# WDUExtensionBoard.net
KiCad netlist of a schematic drawn in Altium Designer
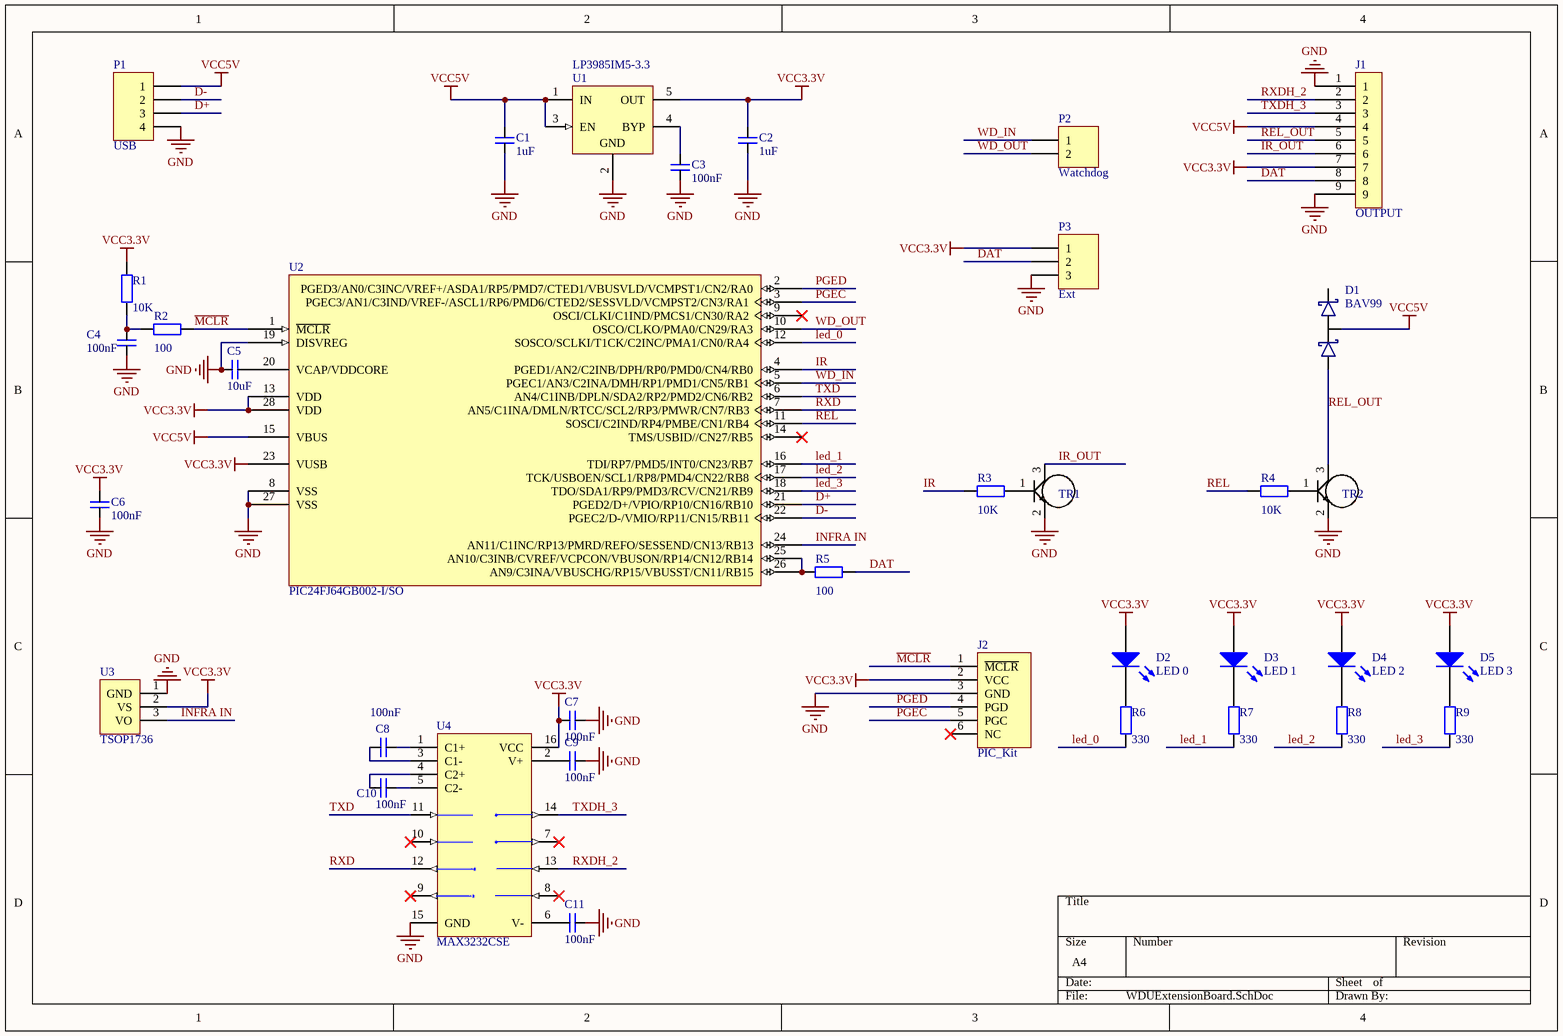
[diagram p0: WDUExtensionBoard.SchDoc]

(export (version "E")
  (design (tool "Eeschema 10.0.6"))
  (components
    (comp (ref "C1")
      (value "1uF")
      (footprint "0805 CAP")
      (description "Capacitor")
      (libsource (lib "EtherIOv2") (part "CAP"))
    )
    (comp (ref "C2")
      (value "1uF")
      (footprint "0805 CAP")
      (description "Capacitor")
      (libsource (lib "EtherIOv2") (part "CAP"))
    )
    (comp (ref "C3")
      (value "100nF")
      (footprint "0805 CAP")
      (description "Capacitor")
      (libsource (lib "EtherIOv2") (part "CAP"))
    )
    (comp (ref "C4")
      (value "100nF")
      (footprint "0805 CAP")
      (description "Capacitor")
      (libsource (lib "EtherIOv2") (part "CAP"))
    )
    (comp (ref "C5")
      (value "10uF")
      (footprint "0805 CAP")
      (description "Capacitor")
      (libsource (lib "EtherIOv2") (part "CAP"))
    )
    (comp (ref "C6")
      (value "100nF")
      (footprint "0805 CAP")
      (description "Capacitor")
      (libsource (lib "EtherIOv2") (part "CAP"))
    )
    (comp (ref "C7")
      (value "100nF")
      (footprint "0805 CAP")
      (description "Capacitor")
      (libsource (lib "EtherIOv2") (part "CAP"))
    )
    (comp (ref "C8")
      (value "100nF")
      (footprint "0805 CAP")
      (description "Capacitor")
      (libsource (lib "EtherIOv2") (part "CAP"))
    )
    (comp (ref "C9")
      (value "100nF")
      (footprint "0805 CAP")
      (description "Capacitor")
      (libsource (lib "EtherIOv2") (part "CAP"))
    )
    (comp (ref "C10")
      (value "100nF")
      (footprint "0805 CAP")
      (description "Capacitor")
      (libsource (lib "EtherIOv2") (part "CAP"))
    )
    (comp (ref "C11")
      (value "100nF")
      (footprint "0805 CAP")
      (description "Capacitor")
      (libsource (lib "EtherIOv2") (part "CAP"))
    )
    (comp (ref "D1")
      (value "BAV99")
      (footprint "SOT23")
      (description "Dual Schottky series - 0.2A, 75V")
      (libsource (lib "EtherIOv2") (part "BAV99"))
    )
    (comp (ref "D2")
      (value "LED 0")
      (footprint "1206 LED Reversed")
      (description "Typical RED, GREEN, YELLOW, AMBER GaAs LED")
      (fields (field (name "PUBLISHER") "Altium Limited"))
      (libsource (lib "Miscellaneous Devices") (part "LED2"))
    )
    (comp (ref "D3")
      (value "LED 1")
      (footprint "1206 LED Reversed")
      (description "Typical RED, GREEN, YELLOW, AMBER GaAs LED")
      (fields (field (name "PUBLISHER") "Altium Limited"))
      (libsource (lib "Miscellaneous Devices") (part "LED2"))
    )
    (comp (ref "D4")
      (value "LED 2")
      (footprint "1206 LED Reversed")
      (description "Typical RED, GREEN, YELLOW, AMBER GaAs LED")
      (fields (field (name "PUBLISHER") "Altium Limited"))
      (libsource (lib "Miscellaneous Devices") (part "LED2"))
    )
    (comp (ref "D5")
      (value "LED 3")
      (footprint "1206 LED Reversed")
      (description "Typical RED, GREEN, YELLOW, AMBER GaAs LED")
      (fields (field (name "PUBLISHER") "Altium Limited"))
      (libsource (lib "Miscellaneous Devices") (part "LED2"))
    )
    (comp (ref "J1")
      (value "OUTPUT")
      (footprint "Euroblock 3.5pitch 9P")
      (libsource (lib "EtherIOv2") (part "Euroblock 9P connector"))
    )
    (comp (ref "J2")
      (value "PIC_Kit")
      (footprint "HDR1X6")
      (description "PIC Kit connector")
      (libsource (lib "EtherIOv2") (part "PIC_Kit"))
    )
    (comp (ref "P1")
      (value "USB")
      (footprint "HDR1X4")
      (description "Header, 4-Pin")
      (fields (field (name "PUBLISHER") "Altium Limited"))
      (libsource (lib "Miscellaneous Connectors") (part "Header 4"))
    )
    (comp (ref "P2")
      (value "Watchdog")
      (footprint "HDR1X2")
      (description "Header, 2-Pin")
      (fields (field (name "PUBLISHER") "Altium Limited"))
      (libsource (lib "Miscellaneous Connectors") (part "Header 2"))
    )
    (comp (ref "P3")
      (value "Ext")
      (footprint "HDR1X3")
      (description "Header, 3-Pin")
      (fields (field (name "PUBLISHER") "Altium Limited"))
      (libsource (lib "Miscellaneous Connectors") (part "Header 3"))
    )
    (comp (ref "R1")
      (value "10K")
      (footprint "0805 RES")
      (description "Resistor")
      (fields (field (name "PUBLISHER") "Altium Limited"))
      (libsource (lib "") (part "RES_2"))
    )
    (comp (ref "R2")
      (value "100")
      (footprint "0805 RES")
      (description "Resistor")
      (fields (field (name "PUBLISHER") "Altium Limited"))
      (libsource (lib "EtherIOv2") (part "RES"))
    )
    (comp (ref "R3")
      (value "10K")
      (footprint "0805 RES")
      (description "Resistor")
      (fields (field (name "PUBLISHER") "Altium Limited"))
      (libsource (lib "EtherIOv2") (part "RES"))
    )
    (comp (ref "R4")
      (value "10K")
      (footprint "0805 RES")
      (description "Resistor")
      (fields (field (name "PUBLISHER") "Altium Limited"))
      (libsource (lib "EtherIOv2") (part "RES"))
    )
    (comp (ref "R5")
      (value "100")
      (footprint "0805 RES")
      (description "Resistor")
      (fields (field (name "PUBLISHER") "Altium Limited"))
      (libsource (lib "EtherIOv2") (part "RES"))
    )
    (comp (ref "R6")
      (value "330")
      (footprint "0805 RES")
      (description "Resistor")
      (fields (field (name "PUBLISHER") "Altium Limited"))
      (libsource (lib "") (part "RES_1"))
    )
    (comp (ref "R7")
      (value "330")
      (footprint "0805 RES")
      (description "Resistor")
      (fields (field (name "PUBLISHER") "Altium Limited"))
      (libsource (lib "") (part "RES_1"))
    )
    (comp (ref "R8")
      (value "330")
      (footprint "0805 RES")
      (description "Resistor")
      (fields (field (name "PUBLISHER") "Altium Limited"))
      (libsource (lib "") (part "RES_1"))
    )
    (comp (ref "R9")
      (value "330")
      (footprint "0805 RES")
      (description "Resistor")
      (fields (field (name "PUBLISHER") "Altium Limited"))
      (libsource (lib "") (part "RES_1"))
    )
    (comp (ref "TR1")
      (value "BC846")
      (footprint "SOT23")
      (description "NPN Transistor, 80 V, SOT23")
      (libsource (lib "Waterstars") (part "BC846"))
    )
    (comp (ref "TR2")
      (value "BC846")
      (footprint "SOT23")
      (description "NPN Transistor, 80 V, SOT23")
      (libsource (lib "Waterstars") (part "BC846"))
    )
    (comp (ref "U1")
      (value "LP3985IM5-3.3")
      (footprint "MF05A_N")
      (description "Micropower, 150mA Low-Noise Ultra Low-Dropout CMOS Voltage Regulator")
      (fields
        (field (name "MANUFACTURER") "National Semiconductor")
        (field (name "DIGIKEYPARTNUMBER") "LP3985IM5-3.3CT-ND")
        (field (name "PUBLISHER") "Altium Limited")
      )
      (libsource (lib "NSC LDO") (part "LP3985IM5-3.3"))
    )
    (comp (ref "U2")
      (value "PIC24FJ64GB002-I/SO")
      (footprint "SSOP-28")
      (fields (field (name "PUBLISHER") "Altium Limited"))
      (libsource (lib "Waterstars") (part "PIC24FJ64GB002-I/SO"))
    )
    (comp (ref "U3")
      (value "TSOP1736")
      (footprint "TSOP17xx")
      (description "IR Receiver, 3-Pin")
      (fields (field (name "PUBLISHER") "Altium Limited"))
      (libsource (lib "EtherIOv2") (part "TSOP17xx"))
    )
    (comp (ref "U4")
      (value "MAX3232CSE")
      (footprint "NSO16_M")
      (description "3.0V TO 5.5V, Low-Power, up to 1Mbps, True RS-232 Transceiver Using Four 0.1µF External Capacitor")
      (fields (field (name "PUBLISHER") "Altium Limited"))
      (libsource (lib "Maxim Communication Transceiver") (part "MAX3232CSE"))
    )
  )
  (nets
    (net (code "1") (name "/D+") (class "Default")
      (node (ref "P1") (pin "3") (pinfunction "3_3") (pintype "passive"))
      (node (ref "U2") (pin "21") (pinfunction "PGED2/D+/VPIO/RP10/CN16/RB10_21") (pintype "bidirectional"))
    )
    (net (code "2") (name "/D-") (class "Default")
      (node (ref "P1") (pin "2") (pinfunction "2_2") (pintype "passive"))
      (node (ref "U2") (pin "22") (pinfunction "PGEC2/D-/VMIO/RP11/CN15/RB11_22") (pintype "bidirectional"))
    )
    (net (code "3") (name "/DAT") (class "Default")
      (node (ref "J1") (pin "8") (pinfunction "8_8") (pintype "passive"))
      (node (ref "P3") (pin "2") (pinfunction "2_2") (pintype "passive"))
      (node (ref "R5") (pin "1") (pinfunction "1_1") (pintype "passive"))
    )
    (net (code "4") (name "/INFRA IN") (class "Default")
      (node (ref "U2") (pin "24") (pinfunction "AN11/C1INC/RP13/PMRD/REFO/SESSEND/CN13/RB13_24") (pintype "bidirectional"))
      (node (ref "U3") (pin "3") (pinfunction "VO_3") (pintype "passive"))
    )
    (net (code "5") (name "/IR") (class "Default")
      (node (ref "R3") (pin "2") (pinfunction "2_2") (pintype "passive"))
      (node (ref "U2") (pin "4") (pinfunction "PGED1/AN2/C2INB/DPH/RP0/PMD0/CN4/RB0_4") (pintype "bidirectional"))
    )
    (net (code "6") (name "/IR_OUT") (class "Default")
      (node (ref "J1") (pin "6") (pinfunction "6_6") (pintype "passive"))
      (node (ref "TR1") (pin "3") (pinfunction "2_3") (pintype "passive"))
    )
    (net (code "7") (name "/PGEC") (class "Default")
      (node (ref "J2") (pin "5") (pinfunction "PGC_5") (pintype "passive"))
      (node (ref "U2") (pin "3") (pinfunction "PGEC3/AN1/C3IND/VREF-/ASCL1/RP6/PMD6/CTED2/SESSVLD/VCMPST2/CN3/RA1_3") (pintype "bidirectional"))
    )
    (net (code "8") (name "/PGED") (class "Default")
      (node (ref "J2") (pin "4") (pinfunction "PGD_4") (pintype "passive"))
      (node (ref "U2") (pin "2") (pinfunction "PGED3/AN0/C3INC/VREF+/ASDA1/RP5/PMD7/CTED1/VBUSVLD/VCMPST1/CN2/RA0_2") (pintype "bidirectional"))
    )
    (net (code "9") (name "/REL") (class "Default")
      (node (ref "R4") (pin "2") (pinfunction "2_2") (pintype "passive"))
      (node (ref "U2") (pin "11") (pinfunction "SOSCI/C2IND/RP4/PMBE/CN1/RB4_11") (pintype "bidirectional"))
    )
    (net (code "10") (name "/REL_OUT") (class "Default")
      (node (ref "D1") (pin "1") (pintype "passive"))
      (node (ref "J1") (pin "5") (pinfunction "5_5") (pintype "passive"))
      (node (ref "TR2") (pin "3") (pinfunction "2_3") (pintype "passive"))
    )
    (net (code "11") (name "/RXD") (class "Default")
      (node (ref "U2") (pin "7") (pinfunction "AN5/C1INA/DMLN/RTCC/SCL2/RP3/PMWR/CN7/RB3_7") (pintype "bidirectional"))
      (node (ref "U4") (pin "12") (pinfunction "R1OUT_12") (pintype "output"))
    )
    (net (code "12") (name "/RXDH_2") (class "Default")
      (node (ref "J1") (pin "2") (pinfunction "2_2") (pintype "passive"))
      (node (ref "U4") (pin "13") (pinfunction "R1IN_13") (pintype "input"))
    )
    (net (code "13") (name "/TXD") (class "Default")
      (node (ref "U2") (pin "6") (pinfunction "AN4/C1INB/DPLN/SDA2/RP2/PMD2/CN6/RB2_6") (pintype "bidirectional"))
      (node (ref "U4") (pin "11") (pinfunction "T1IN_11") (pintype "input"))
    )
    (net (code "14") (name "/TXDH_3") (class "Default")
      (node (ref "J1") (pin "3") (pinfunction "3_3") (pintype "passive"))
      (node (ref "U4") (pin "14") (pinfunction "T1OUT_14") (pintype "output"))
    )
    (net (code "15") (name "/WD_IN") (class "Default")
      (node (ref "P2") (pin "1") (pinfunction "1_1") (pintype "passive"))
      (node (ref "U2") (pin "5") (pinfunction "PGEC1/AN3/C2INA/DMH/RP1/PMD1/CN5/RB1_5") (pintype "bidirectional"))
    )
    (net (code "16") (name "/WD_OUT") (class "Default")
      (node (ref "P2") (pin "2") (pinfunction "2_2") (pintype "passive"))
      (node (ref "U2") (pin "10") (pinfunction "OSCO/CLKO/PMA0/CN29/RA3_10") (pintype "bidirectional"))
    )
    (net (code "17") (name "/led_0") (class "Default")
      (node (ref "R6") (pin "2") (pinfunction "2_2") (pintype "passive"))
      (node (ref "U2") (pin "12") (pinfunction "SOSCO/SCLKI/T1CK/C2INC/PMA1/CN0/RA4_12") (pintype "bidirectional"))
    )
    (net (code "18") (name "/led_1") (class "Default")
      (node (ref "R7") (pin "2") (pinfunction "2_2") (pintype "passive"))
      (node (ref "U2") (pin "16") (pinfunction "TDI/RP7/PMD5/INT0/CN23/RB7_16") (pintype "bidirectional"))
    )
    (net (code "19") (name "/led_2") (class "Default")
      (node (ref "R8") (pin "2") (pinfunction "2_2") (pintype "passive"))
      (node (ref "U2") (pin "17") (pinfunction "TCK/USBOEN/SCL1/RP8/PMD4/CN22/RB8_17") (pintype "bidirectional"))
    )
    (net (code "20") (name "/led_3") (class "Default")
      (node (ref "R9") (pin "2") (pinfunction "2_2") (pintype "passive"))
      (node (ref "U2") (pin "18") (pinfunction "TDO/SDA1/RP9/PMD3/RCV/CN21/RB9_18") (pintype "bidirectional"))
    )
    (net (code "21") (name "/~{MCLR}") (class "Default")
      (node (ref "J2") (pin "1") (pinfunction "~{MCLR}_1") (pintype "passive"))
      (node (ref "R2") (pin "1") (pinfunction "1_1") (pintype "passive"))
      (node (ref "U2") (pin "1") (pinfunction "~{MCLR}_1") (pintype "input"))
    )
    (net (code "22") (name "GND") (class "Default")
      (node (ref "C1") (pin "1") (pinfunction "A_1") (pintype "passive"))
      (node (ref "C11") (pin "2") (pinfunction "B_2") (pintype "passive"))
      (node (ref "C2") (pin "1") (pinfunction "A_1") (pintype "passive"))
      (node (ref "C3") (pin "1") (pinfunction "A_1") (pintype "passive"))
      (node (ref "C4") (pin "1") (pinfunction "A_1") (pintype "passive"))
      (node (ref "C5") (pin "2") (pinfunction "B_2") (pintype "passive"))
      (node (ref "C6") (pin "1") (pinfunction "A_1") (pintype "passive"))
      (node (ref "C7") (pin "2") (pinfunction "B_2") (pintype "passive"))
      (node (ref "C9") (pin "2") (pinfunction "B_2") (pintype "passive"))
      (node (ref "J1") (pin "1") (pinfunction "1_1") (pintype "passive"))
      (node (ref "J1") (pin "9") (pinfunction "9_9") (pintype "passive"))
      (node (ref "J2") (pin "3") (pinfunction "GND_3") (pintype "passive"))
      (node (ref "P1") (pin "4") (pinfunction "4_4") (pintype "passive"))
      (node (ref "P3") (pin "3") (pinfunction "3_3") (pintype "passive"))
      (node (ref "TR1") (pin "2") (pinfunction "1_2") (pintype "passive"))
      (node (ref "TR2") (pin "2") (pinfunction "1_2") (pintype "passive"))
      (node (ref "U1") (pin "2") (pinfunction "GND_2") (pintype "power_in"))
      (node (ref "U2") (pin "19") (pinfunction "DISVREG_19") (pintype "input"))
      (node (ref "U2") (pin "27") (pinfunction "VSS_27") (pintype "power_in"))
      (node (ref "U2") (pin "8") (pinfunction "VSS_8") (pintype "power_in"))
      (node (ref "U3") (pin "1") (pinfunction "GND_1") (pintype "passive"))
      (node (ref "U4") (pin "15") (pinfunction "GND_15") (pintype "power_in"))
    )
    (net (code "23") (name "Net-(C3-B)") (class "Default")
      (node (ref "C3") (pin "2") (pinfunction "B_2") (pintype "passive"))
      (node (ref "U1") (pin "4") (pinfunction "BYP_4") (pintype "passive"))
    )
    (net (code "24") (name "Net-(C4-B)") (class "Default")
      (node (ref "C4") (pin "2") (pinfunction "B_2") (pintype "passive"))
      (node (ref "R1") (pin "1") (pinfunction "1_1") (pintype "passive"))
      (node (ref "R2") (pin "2") (pinfunction "2_2") (pintype "passive"))
    )
    (net (code "25") (name "Net-(C5-A)") (class "Default")
      (node (ref "C5") (pin "1") (pinfunction "A_1") (pintype "passive"))
      (node (ref "U2") (pin "20") (pinfunction "VCAP/VDDCORE_20") (pintype "power_in"))
    )
    (net (code "26") (name "Net-(C8-A)") (class "Default")
      (node (ref "C8") (pin "1") (pinfunction "A_1") (pintype "passive"))
      (node (ref "U4") (pin "3") (pinfunction "C1-_3") (pintype "passive"))
    )
    (net (code "27") (name "Net-(C8-B)") (class "Default")
      (node (ref "C8") (pin "2") (pinfunction "B_2") (pintype "passive"))
      (node (ref "U4") (pin "1") (pinfunction "C1+_1") (pintype "passive"))
    )
    (net (code "28") (name "Net-(C9-A)") (class "Default")
      (node (ref "C9") (pin "1") (pinfunction "A_1") (pintype "passive"))
      (node (ref "U4") (pin "2") (pinfunction "V+_2") (pintype "power_in"))
    )
    (net (code "29") (name "Net-(C10-A)") (class "Default")
      (node (ref "C10") (pin "1") (pinfunction "A_1") (pintype "passive"))
      (node (ref "U4") (pin "4") (pinfunction "C2+_4") (pintype "passive"))
    )
    (net (code "30") (name "Net-(C10-B)") (class "Default")
      (node (ref "C10") (pin "2") (pinfunction "B_2") (pintype "passive"))
      (node (ref "U4") (pin "5") (pinfunction "C2-_5") (pintype "passive"))
    )
    (net (code "31") (name "Net-(C11-A)") (class "Default")
      (node (ref "C11") (pin "1") (pinfunction "A_1") (pintype "passive"))
      (node (ref "U4") (pin "6") (pinfunction "V-_6") (pintype "power_in"))
    )
    (net (code "32") (name "Net-(D2-K)") (class "Default")
      (node (ref "D2") (pin "2") (pinfunction "K_2") (pintype "passive"))
      (node (ref "R6") (pin "1") (pinfunction "1_1") (pintype "passive"))
    )
    (net (code "33") (name "Net-(D3-K)") (class "Default")
      (node (ref "D3") (pin "2") (pinfunction "K_2") (pintype "passive"))
      (node (ref "R7") (pin "1") (pinfunction "1_1") (pintype "passive"))
    )
    (net (code "34") (name "Net-(D4-K)") (class "Default")
      (node (ref "D4") (pin "2") (pinfunction "K_2") (pintype "passive"))
      (node (ref "R8") (pin "1") (pinfunction "1_1") (pintype "passive"))
    )
    (net (code "35") (name "Net-(D5-K)") (class "Default")
      (node (ref "D5") (pin "2") (pinfunction "K_2") (pintype "passive"))
      (node (ref "R9") (pin "1") (pinfunction "1_1") (pintype "passive"))
    )
    (net (code "36") (name "Net-(TR1-B)") (class "Default")
      (node (ref "R3") (pin "1") (pinfunction "1_1") (pintype "passive"))
      (node (ref "TR1") (pin "1") (pinfunction "B_1") (pintype "passive"))
    )
    (net (code "37") (name "Net-(TR2-B)") (class "Default")
      (node (ref "R4") (pin "1") (pinfunction "1_1") (pintype "passive"))
      (node (ref "TR2") (pin "1") (pinfunction "B_1") (pintype "passive"))
    )
    (net (code "38") (name "Net-(U2-AN10{slash}C3INB{slash}CVREF{slash}VCPCON{slash}VBUSON{slash}RP14{slash}CN12{slash}RB14)") (class "Default")
      (node (ref "R5") (pin "2") (pinfunction "2_2") (pintype "passive"))
      (node (ref "U2") (pin "25") (pinfunction "AN10/C3INB/CVREF/VCPCON/VBUSON/RP14/CN12/RB14_25") (pintype "bidirectional"))
      (node (ref "U2") (pin "26") (pinfunction "AN9/C3INA/VBUSCHG/RP15/VBUSST/CN11/RB15_26") (pintype "bidirectional"))
    )
    (net (code "39") (name "VCC3.3V") (class "Default")
      (node (ref "C2") (pin "2") (pinfunction "B_2") (pintype "passive"))
      (node (ref "C6") (pin "2") (pinfunction "B_2") (pintype "passive"))
      (node (ref "C7") (pin "1") (pinfunction "A_1") (pintype "passive"))
      (node (ref "D2") (pin "1") (pinfunction "A_1") (pintype "passive"))
      (node (ref "D3") (pin "1") (pinfunction "A_1") (pintype "passive"))
      (node (ref "D4") (pin "1") (pinfunction "A_1") (pintype "passive"))
      (node (ref "D5") (pin "1") (pinfunction "A_1") (pintype "passive"))
      (node (ref "J1") (pin "7") (pinfunction "7_7") (pintype "passive"))
      (node (ref "J2") (pin "2") (pinfunction "VCC_2") (pintype "passive"))
      (node (ref "P3") (pin "1") (pinfunction "1_1") (pintype "passive"))
      (node (ref "R1") (pin "2") (pinfunction "2_2") (pintype "passive"))
      (node (ref "U1") (pin "5") (pinfunction "OUT_5") (pintype "power_in"))
      (node (ref "U2") (pin "13") (pinfunction "VDD_13") (pintype "power_in"))
      (node (ref "U2") (pin "23") (pinfunction "VUSB_23") (pintype "power_in"))
      (node (ref "U2") (pin "28") (pinfunction "VDD_28") (pintype "power_in"))
      (node (ref "U3") (pin "2") (pinfunction "VS_2") (pintype "passive"))
      (node (ref "U4") (pin "16") (pinfunction "VCC_16") (pintype "power_in"))
    )
    (net (code "40") (name "VCC5V") (class "Default")
      (node (ref "C1") (pin "2") (pinfunction "B_2") (pintype "passive"))
      (node (ref "D1") (pin "3") (pintype "passive"))
      (node (ref "J1") (pin "4") (pinfunction "4_4") (pintype "passive"))
      (node (ref "P1") (pin "1") (pinfunction "1_1") (pintype "passive"))
      (node (ref "U1") (pin "1") (pinfunction "IN_1") (pintype "power_in"))
      (node (ref "U1") (pin "3") (pinfunction "EN_3") (pintype "input"))
      (node (ref "U2") (pin "15") (pinfunction "VBUS_15") (pintype "power_in"))
    )
    (net (code "41") (name "unconnected-(D1-Pad2)") (class "Default")
      (node (ref "D1") (pin "2") (pintype "passive"))
    )
    (net (code "42") (name "unconnected-(J2-NC-Pad6)") (class "Default")
      (node (ref "J2") (pin "6") (pinfunction "NC_6") (pintype "passive+no_connect"))
    )
    (net (code "43") (name "unconnected-(U2-OSCI{slash}CLKI{slash}C1IND{slash}PMCS1{slash}CN30{slash}RA2-Pad9)") (class "Default")
      (node (ref "U2") (pin "9") (pinfunction "OSCI/CLKI/C1IND/PMCS1/CN30/RA2_9") (pintype "bidirectional+no_connect"))
    )
    (net (code "44") (name "unconnected-(U2-TMS{slash}USBID{slash}{slash}CN27{slash}RB5-Pad14)") (class "Default")
      (node (ref "U2") (pin "14") (pinfunction "TMS/USBID//CN27/RB5_14") (pintype "bidirectional+no_connect"))
    )
    (net (code "45") (name "unconnected-(U4-R2IN-Pad8)") (class "Default")
      (node (ref "U4") (pin "8") (pinfunction "R2IN_8") (pintype "input+no_connect"))
    )
    (net (code "46") (name "unconnected-(U4-R2OUT-Pad9)") (class "Default")
      (node (ref "U4") (pin "9") (pinfunction "R2OUT_9") (pintype "output+no_connect"))
    )
    (net (code "47") (name "unconnected-(U4-T2IN-Pad10)") (class "Default")
      (node (ref "U4") (pin "10") (pinfunction "T2IN_10") (pintype "input+no_connect"))
    )
    (net (code "48") (name "unconnected-(U4-T2OUT-Pad7)") (class "Default")
      (node (ref "U4") (pin "7") (pinfunction "T2OUT_7") (pintype "output+no_connect"))
    )
  )
)
